# 1_040_1573_rev01_reg.net
KiCad netlist of a schematic drawn in Altium Designer
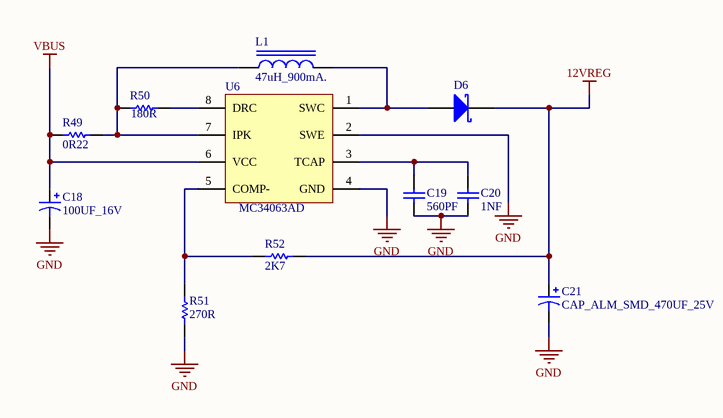
[diagram p0: 1 040 1573.rev01_reg.SchDoc]

(export (version "E")
  (design (tool "Eeschema 10.0.6"))
  (components
    (comp (ref "C18")
      (value "100UF_16V")
      (footprint "0505(47uF/35V)")
      (description "1 043 0020")
      (fields (field (name "PUBLISHER") "Altium Limited"))
      (libsource (lib "Sanel_Lib_V1") (part "CAP_ALM_SMD_100UF_16V_1"))
    )
    (comp (ref "C19")
      (value "560PF")
      (footprint "Capacitor(0603)-1")
      (description "1 043 0220")
      (fields (field (name "PUBLISHER") "Altium Limited"))
      (libsource (lib "Sanel_Lib_V1") (part "CAP_CER_SMD_560PF_50V_0603"))
    )
    (comp (ref "C20")
      (value "1NF")
      (footprint "Capacitor(0603)-1")
      (description "1 043 0109")
      (fields (field (name "PUBLISHER") "Altium Limited"))
      (libsource (lib "Sanel_Lib_V1") (part "CAP_CER_SMD_1NF_50V_0603"))
    )
    (comp (ref "C21")
      (value "CAP_ALM_SMD_470UF_25V")
      (footprint "0505(470uF/25V)")
      (description "1 043 0043")
      (fields (field (name "PUBLISHER") "Altium Limited"))
      (libsource (lib "Sanel_Lib_V1") (part "CAP_ALM_SMD_470UF_25V"))
    )
    (comp (ref "D6")
      (value "DIODE_SCHOTTKY_50V_3A_DO214AA_SR35")
      (footprint "SMB_0")
      (description "1 044 0063")
      (fields (field (name "PUBLISHER") "Altium Limited"))
      (libsource (lib "Sanel_Lib_V1") (part "DIODE_SCHOTTKY_50V_3A_DO214AA_SR35"))
    )
    (comp (ref "L1")
      (value "47uH_900mA.")
      (footprint "SMD_inductor(900mA)")
      (description "1 048 0071")
      (libsource (lib "Sanel_Lib_V1") (part "47uH_900mA. Coil"))
    )
    (comp (ref "R49")
      (value "0R22")
      (footprint "Resistor(0805) -1")
      (description "1 042 0614")
      (fields (field (name "PUBLISHER") "Altium Limited"))
      (libsource (lib "Sanel_Lib_V1") (part "RES_SMD_0R22_%5_0805"))
    )
    (comp (ref "R50")
      (value "180R")
      (footprint "Resistor(0603) -1")
      (description "1 042 0558")
      (fields (field (name "PUBLISHER") "Altium Limited"))
      (libsource (lib "Sanel_Lib_V1") (part "RES_SMD_180R_%5_0603"))
    )
    (comp (ref "R51")
      (value "270R")
      (footprint "Resistor(0603) -1")
      (description "1 042 0622")
      (fields (field (name "PUBLISHER") "Altium Limited"))
      (libsource (lib "Sanel_Lib_V1") (part "RES_SMD_270R_%1_0603"))
    )
    (comp (ref "R52")
      (value "2K7")
      (footprint "Resistor(0603) -1")
      (description "1 042 0625")
      (fields (field (name "PUBLISHER") "Altium Limited"))
      (libsource (lib "Sanel_Lib_V1") (part "RES_SMD_2K7_%1_0603"))
    )
    (comp (ref "U6")
      (value "MC34063AD")
      (footprint "SO-8")
      (description "1 046 0094 (UTC)")
      (fields (field (name "PARTNUMBER") "MC34063ADR") (field (name "MANUFACTURER") "Texas Instruments"))
      (libsource (lib "Sanel_Lib_V1") (part "IC_REG_SMD_SOIC8_TI_MC34063AD"))
    )
  )
  (nets
    (net (code "1") (name "12VREG") (class "Default")
      (node (ref "C21") (pin "1") (pinfunction "1_1") (pintype "passive"))
      (node (ref "D6") (pin "2") (pinfunction "K_2") (pintype "passive"))
      (node (ref "R52") (pin "2") (pinfunction "2_2") (pintype "passive"))
    )
    (net (code "2") (name "GND") (class "Default")
      (node (ref "C18") (pin "2") (pinfunction "2_2") (pintype "passive"))
      (node (ref "C19") (pin "1") (pinfunction "1_1") (pintype "passive"))
      (node (ref "C20") (pin "1") (pinfunction "1_1") (pintype "passive"))
      (node (ref "C21") (pin "2") (pinfunction "2_2") (pintype "passive"))
      (node (ref "R51") (pin "1") (pinfunction "1_1") (pintype "passive"))
      (node (ref "U6") (pin "2") (pinfunction "SWE_2") (pintype "passive"))
      (node (ref "U6") (pin "4") (pinfunction "GND_4") (pintype "passive"))
    )
    (net (code "3") (name "Net-(D6-A)") (class "Default")
      (node (ref "D6") (pin "1") (pinfunction "A_1") (pintype "passive"))
      (node (ref "L1") (pin "2") (pinfunction "2_2") (pintype "passive"))
      (node (ref "U6") (pin "1") (pinfunction "SWC_1") (pintype "open_collector"))
    )
    (net (code "4") (name "Net-(U6-COMP-)") (class "Default")
      (node (ref "R51") (pin "2") (pinfunction "2_2") (pintype "passive"))
      (node (ref "R52") (pin "1") (pinfunction "1_1") (pintype "passive"))
      (node (ref "U6") (pin "5") (pinfunction "COMP-_5") (pintype "passive"))
    )
    (net (code "5") (name "Net-(U6-DRC)") (class "Default")
      (node (ref "R50") (pin "2") (pinfunction "2_2") (pintype "passive"))
      (node (ref "U6") (pin "8") (pinfunction "DRC_8") (pintype "open_collector"))
    )
    (net (code "6") (name "Net-(U6-IPK)") (class "Default")
      (node (ref "L1") (pin "1") (pinfunction "1_1") (pintype "passive"))
      (node (ref "R49") (pin "2") (pinfunction "2_2") (pintype "passive"))
      (node (ref "R50") (pin "1") (pinfunction "1_1") (pintype "passive"))
      (node (ref "U6") (pin "7") (pinfunction "IPK_7") (pintype "passive"))
    )
    (net (code "7") (name "Net-(U6-TCAP)") (class "Default")
      (node (ref "C19") (pin "2") (pinfunction "2_2") (pintype "passive"))
      (node (ref "C20") (pin "2") (pinfunction "2_2") (pintype "passive"))
      (node (ref "U6") (pin "3") (pinfunction "TCAP_3") (pintype "passive"))
    )
    (net (code "8") (name "VBUS") (class "Default")
      (node (ref "C18") (pin "1") (pinfunction "1_1") (pintype "passive"))
      (node (ref "R49") (pin "1") (pinfunction "1_1") (pintype "passive"))
      (node (ref "U6") (pin "6") (pinfunction "VCC_6") (pintype "power_in"))
    )
  )
)
